# Power.net
KiCad netlist of a schematic drawn in Altium Designer
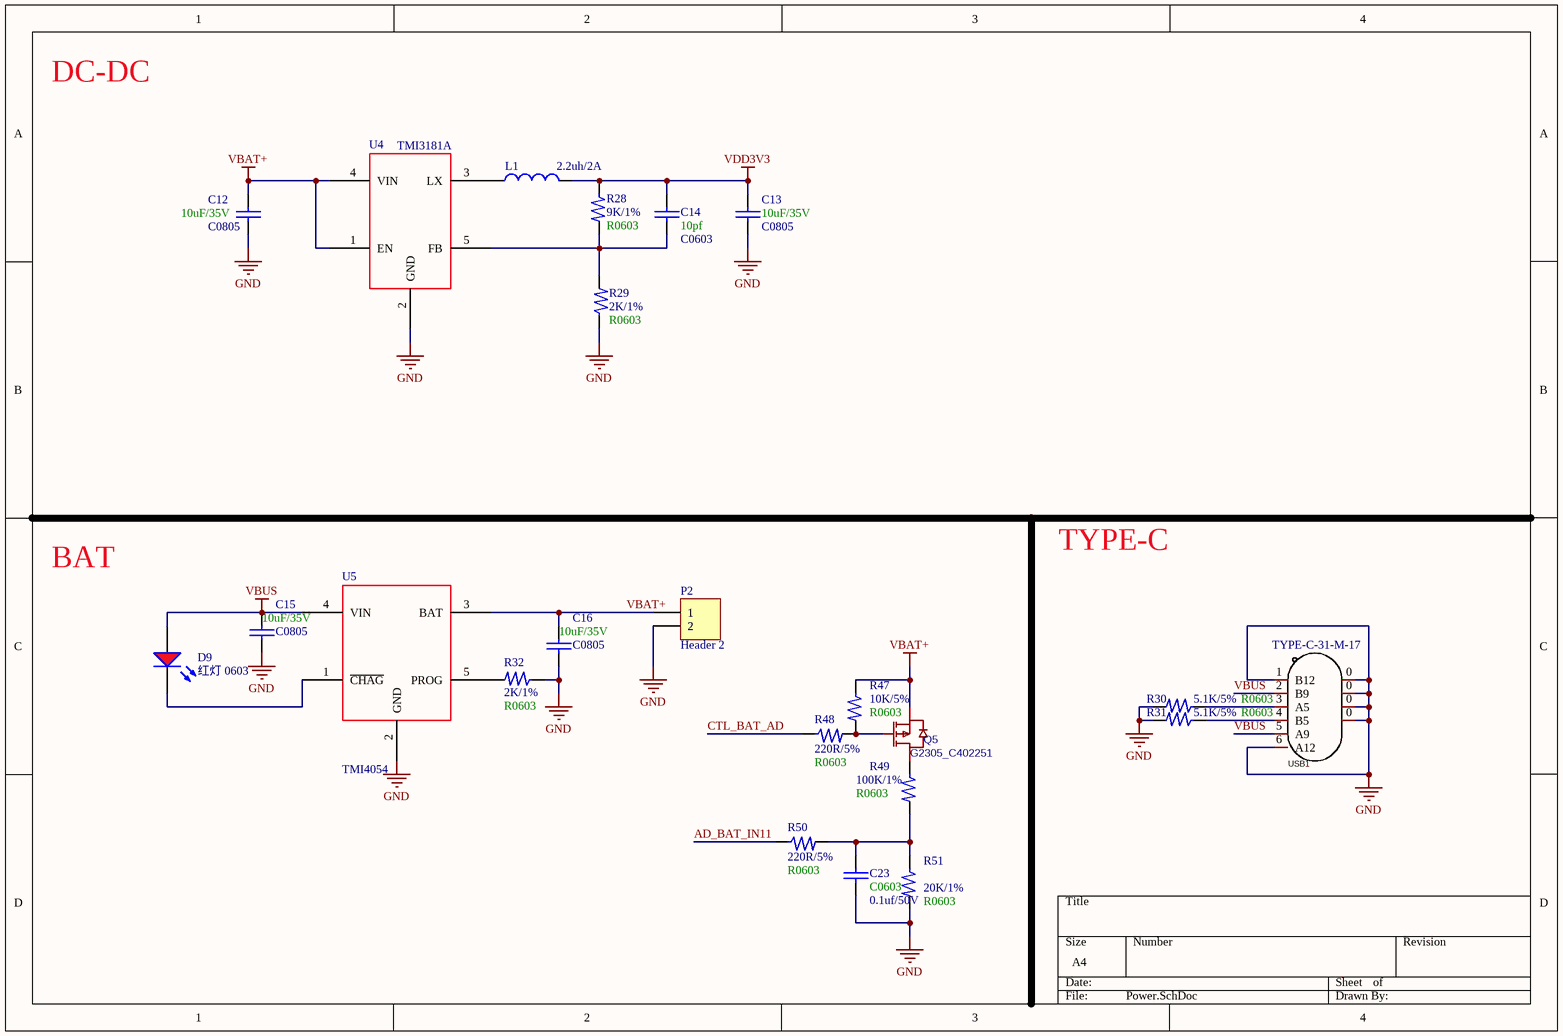
[diagram p0: Power.SchDoc]

(export (version "E")
  (design (tool "Eeschema 10.0.6"))
  (components
    (comp (ref "C12")
      (value "10uF/35V")
      (footprint "0805_C")
      (description "10uf/35V")
      (fields (field (name "ALTIUM_VALUE") "C0805"))
      (libsource (lib "*") (part "CAP"))
    )
    (comp (ref "C13")
      (value "10uF/35V")
      (footprint "0805_C")
      (description "10uf/35V")
      (fields (field (name "ALTIUM_VALUE") "C0805"))
      (libsource (lib "*") (part "CAP"))
    )
    (comp (ref "C14")
      (value "10pf")
      (footprint "0603_C")
      (fields (field (name "ALTIUM_VALUE") "C0603"))
      (libsource (lib "*") (part "CAP"))
    )
    (comp (ref "C15")
      (value "10uF/35V")
      (footprint "0805_C")
      (description "10uf/35V")
      (fields (field (name "ALTIUM_VALUE") "C0805"))
      (libsource (lib "*") (part "CAP"))
    )
    (comp (ref "C16")
      (value "10uF/35V")
      (footprint "0805_C")
      (description "10uf/35V")
      (fields (field (name "ALTIUM_VALUE") "C0805"))
      (libsource (lib "*") (part "CAP"))
    )
    (comp (ref "C23")
      (value "C0603")
      (footprint "0603_C")
      (description "0.1uf/50V")
      (fields (field (name "ALTIUM_VALUE") "0.1uf/50V"))
      (libsource (lib "*") (part "CAP"))
    )
    (comp (ref "D9")
      (value "红灯 0603")
      (footprint "0603_LED_S1")
      (description "发光二极管")
      (libsource (lib "Miscellaneous Devices LC") (part "0603 红灯"))
    )
    (comp (ref "L1") (value "2.2uh/2A") (footprint "IND-SMD_L3.0-W3.0") (libsource (lib "*") (part "L")))
    (comp (ref "P2")
      (value "Header 2")
      (footprint "CONN-TH_2P-P2.50_XH-2AW")
      (description "Header, 2-Pin")
      (fields (field (name "PUBLISHER") "Altium Limited"))
      (libsource (lib "Miscellaneous Connectors") (part "Header 2"))
    )
    (comp (ref "Q5")
      (value "G2305_C402251")
      (footprint "SOT-23-3L")
      (fields
        (field (name "BOM_SUPPLIER PART") "C402251")
        (field (name "BOM_MANUFACTURER PART") "G2305")
        (field (name "CONTRIBUTOR") "LCSC")
      )
      (libsource (lib "altium-import") (part "root_2_mirrored_G2305_C402251_"))
    )
    (comp (ref "R28") (value "9K/1%") (footprint "R0603") (libsource (lib "*") (part "电阻")))
    (comp (ref "R29") (value "2K/1%") (footprint "R0603") (libsource (lib "*") (part "电阻")))
    (comp (ref "R30") (value "5.1K/5%") (footprint "R0603") (libsource (lib "*") (part "电阻")))
    (comp (ref "R31") (value "5.1K/5%") (footprint "R0603") (libsource (lib "*") (part "电阻")))
    (comp (ref "R32") (value "2K/1%") (footprint "R0603") (libsource (lib "*") (part "电阻")))
    (comp (ref "R47") (value "10K/5%") (footprint "R0603") (libsource (lib "*") (part "电阻")))
    (comp (ref "R48") (value "220R/5%") (footprint "R0603") (libsource (lib "*") (part "电阻")))
    (comp (ref "R49") (value "100K/1%") (footprint "R0603") (libsource (lib "*") (part "电阻")))
    (comp (ref "R50") (value "220R/5%") (footprint "R0603") (libsource (lib "*") (part "电阻")))
    (comp (ref "R51") (value "20K/1%") (footprint "R0603") (libsource (lib "*") (part "电阻")))
    (comp (ref "U4") (value "TMI3181A") (footprint "SOT-23-5") (libsource (lib "Schlib1") (part "TMI3181A")))
    (comp (ref "U5") (value "TMI4054") (footprint "SOT-23-5") (libsource (lib "Schlib1") (part "TMI4054")))
    (comp (ref "USB1")
      (value "TYPE-C-31-M-17")
      (footprint "USB-C-SMD_10P-P1.00-L6.8-W8.9")
      (fields (field (name "MANUFACTURER") "韩国韩荣"))
      (libsource (lib "altium-import") (part "root_0_mirrored_TYPE-C-31-M-17_"))
    )
  )
  (nets
    (net (code "1") (name "/AD_BAT_IN11") (class "Default") (node (ref "R50") (pin "2") (pintype "passive")))
    (net (code "2") (name "/CTL_BAT_AD") (class "Default") (node (ref "R48") (pin "2") (pintype "passive")))
    (net (code "3") (name "GND") (class "Default")
      (node (ref "C12") (pin "2") (pinfunction "2_2") (pintype "passive"))
      (node (ref "C13") (pin "2") (pinfunction "2_2") (pintype "passive"))
      (node (ref "C15") (pin "2") (pinfunction "2_2") (pintype "passive"))
      (node (ref "C16") (pin "2") (pinfunction "2_2") (pintype "passive"))
      (node (ref "C23") (pin "2") (pinfunction "2_2") (pintype "passive"))
      (node (ref "P2") (pin "2") (pinfunction "2_2") (pintype "passive"))
      (node (ref "R29") (pin "2") (pintype "passive"))
      (node (ref "R30") (pin "1") (pintype "passive"))
      (node (ref "R31") (pin "1") (pintype "passive"))
      (node (ref "R32") (pin "2") (pintype "passive"))
      (node (ref "R51") (pin "1") (pintype "passive"))
      (node (ref "U4") (pin "2") (pinfunction "GND_2") (pintype "passive"))
      (node (ref "U5") (pin "2") (pinfunction "GND_2") (pintype "passive"))
      (node (ref "USB1") (pin "0") (pinfunction "0_0") (pintype "passive"))
      (node (ref "USB1") (pin "1") (pinfunction "B12_1") (pintype "passive"))
      (node (ref "USB1") (pin "6") (pinfunction "A12_6") (pintype "passive"))
    )
    (net (code "4") (name "Net-(C23-Pad1)") (class "Default")
      (node (ref "C23") (pin "1") (pinfunction "1_1") (pintype "passive"))
      (node (ref "R49") (pin "1") (pintype "passive"))
      (node (ref "R50") (pin "1") (pintype "passive"))
      (node (ref "R51") (pin "2") (pintype "passive"))
    )
    (net (code "5") (name "Net-(Q5-D)") (class "Default")
      (node (ref "Q5") (pin "3") (pinfunction "D_3") (pintype "passive"))
      (node (ref "R49") (pin "2") (pintype "passive"))
    )
    (net (code "6") (name "Net-(Q5-G)") (class "Default")
      (node (ref "Q5") (pin "1") (pinfunction "G_1") (pintype "passive"))
      (node (ref "R47") (pin "1") (pintype "passive"))
      (node (ref "R48") (pin "1") (pintype "passive"))
    )
    (net (code "7") (name "Net-(U4-FB)") (class "Default")
      (node (ref "C14") (pin "1") (pinfunction "1_1") (pintype "passive"))
      (node (ref "R28") (pin "1") (pintype "passive"))
      (node (ref "R29") (pin "1") (pintype "passive"))
      (node (ref "U4") (pin "5") (pinfunction "FB_5") (pintype "passive"))
    )
    (net (code "8") (name "Net-(U4-LX)") (class "Default")
      (node (ref "L1") (pin "2") (pinfunction "2_2") (pintype "passive"))
      (node (ref "U4") (pin "3") (pinfunction "LX_3") (pintype "passive"))
    )
    (net (code "9") (name "Net-(U5-PROG)") (class "Default")
      (node (ref "R32") (pin "1") (pintype "passive"))
      (node (ref "U5") (pin "5") (pinfunction "PROG_5") (pintype "passive"))
    )
    (net (code "10") (name "Net-(U5-~{CHAG})") (class "Default")
      (node (ref "D9") (pin "K") (pinfunction "K_K") (pintype "passive"))
      (node (ref "U5") (pin "1") (pinfunction "~{CHAG}_1") (pintype "passive"))
    )
    (net (code "11") (name "Net-(USB1-A5)") (class "Default")
      (node (ref "R30") (pin "2") (pintype "passive"))
      (node (ref "USB1") (pin "3") (pinfunction "A5_3") (pintype "passive"))
    )
    (net (code "12") (name "Net-(USB1-B5)") (class "Default")
      (node (ref "R31") (pin "2") (pintype "passive"))
      (node (ref "USB1") (pin "4") (pinfunction "B5_4") (pintype "passive"))
    )
    (net (code "13") (name "VBAT+") (class "Default")
      (node (ref "C12") (pin "1") (pinfunction "1_1") (pintype "passive"))
      (node (ref "C16") (pin "1") (pinfunction "1_1") (pintype "passive"))
      (node (ref "P2") (pin "1") (pinfunction "1_1") (pintype "passive"))
      (node (ref "Q5") (pin "2") (pinfunction "S_2") (pintype "passive"))
      (node (ref "R47") (pin "2") (pintype "passive"))
      (node (ref "U4") (pin "1") (pinfunction "EN_1") (pintype "passive"))
      (node (ref "U4") (pin "4") (pinfunction "VIN_4") (pintype "passive"))
      (node (ref "U5") (pin "3") (pinfunction "BAT_3") (pintype "passive"))
    )
    (net (code "14") (name "VBUS") (class "Default")
      (node (ref "C15") (pin "1") (pinfunction "1_1") (pintype "passive"))
      (node (ref "D9") (pin "A") (pinfunction "A_A") (pintype "passive"))
      (node (ref "U5") (pin "4") (pinfunction "VIN_4") (pintype "passive"))
      (node (ref "USB1") (pin "2") (pinfunction "B9_2") (pintype "passive"))
      (node (ref "USB1") (pin "5") (pinfunction "A9_5") (pintype "passive"))
    )
    (net (code "15") (name "VDD3V3") (class "Default")
      (node (ref "C13") (pin "1") (pinfunction "1_1") (pintype "passive"))
      (node (ref "C14") (pin "2") (pinfunction "2_2") (pintype "passive"))
      (node (ref "L1") (pin "1") (pinfunction "1_1") (pintype "passive"))
      (node (ref "R28") (pin "2") (pintype "passive"))
    )
  )
)
